# FE1_1S.net
KiCad netlist of a schematic drawn in Altium Designer
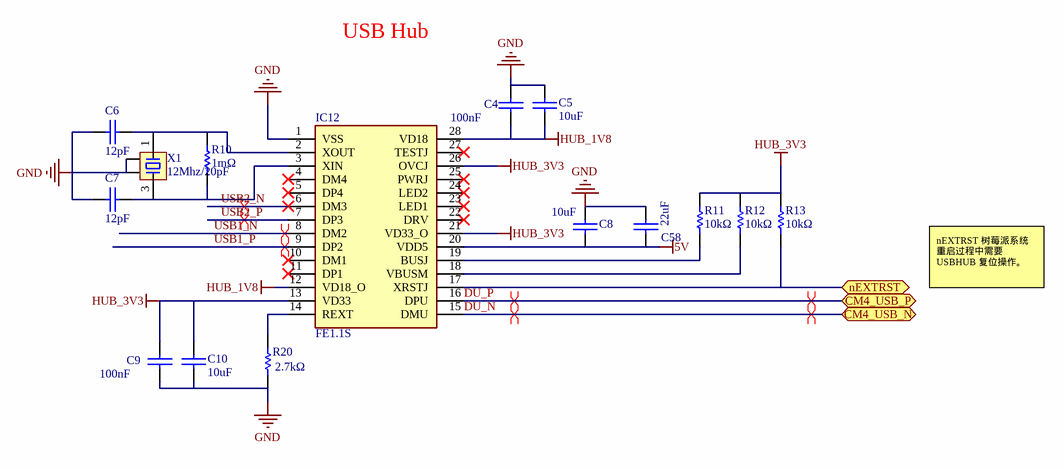
[diagram p0: FE1.1S.SchDoc]

(export (version "E")
  (design (tool "Eeschema 10.0.6"))
  (components
    (comp (ref "C4")
      (value "100nF")
      (footprint "C_0402")
      (description "贴片电容")
      (libsource (lib "IntLib-Passive") (part "Cap_Chip"))
    )
    (comp (ref "C5")
      (value "10uF")
      (footprint "C_0603")
      (description "贴片电容")
      (libsource (lib "IntLib-Passive") (part "Cap_Chip"))
    )
    (comp (ref "C6")
      (value "12pF")
      (footprint "C_0402")
      (description "贴片电容")
      (libsource (lib "IntLib-Passive") (part "Cap_Chip"))
    )
    (comp (ref "C7")
      (value "12pF")
      (footprint "C_0402")
      (description "贴片电容")
      (libsource (lib "IntLib-Passive") (part "Cap_Chip"))
    )
    (comp (ref "C8")
      (value "10uF")
      (footprint "C_0603")
      (description "贴片电容")
      (libsource (lib "IntLib-Passive") (part "Cap_Chip"))
    )
    (comp (ref "C9")
      (value "100nF")
      (footprint "C_0402")
      (description "贴片电容")
      (libsource (lib "IntLib-Passive") (part "Cap_Chip"))
    )
    (comp (ref "C10")
      (value "10uF")
      (footprint "C_0603")
      (description "贴片电容")
      (libsource (lib "IntLib-Passive") (part "Cap_Chip"))
    )
    (comp (ref "C58")
      (value "22uF")
      (footprint "C_0805")
      (description "贴片电容")
      (libsource (lib "IntLib-Passive") (part "Cap_Chip"))
    )
    (comp (ref "IC12")
      (value "FE1.1S")
      (footprint "SamacSys:SOP64P600X175-28N")
      (description "Integrated Circuit")
      (libsource (lib "*") (part "FE1.1S"))
    )
    (comp (ref "R10")
      (value "1mΩ")
      (footprint "R_0402")
      (description "贴片电阻")
      (libsource (lib "IntLib-Passive") (part "Res_Chip"))
    )
    (comp (ref "R11")
      (value "10kΩ")
      (footprint "R_0402")
      (description "贴片电阻")
      (libsource (lib "IntLib-Passive") (part "Res_Chip"))
    )
    (comp (ref "R12")
      (value "10kΩ")
      (footprint "R_0402")
      (description "贴片电阻")
      (libsource (lib "IntLib-Passive") (part "Res_Chip"))
    )
    (comp (ref "R13")
      (value "10kΩ")
      (footprint "R_0402")
      (description "贴片电阻")
      (libsource (lib "IntLib-Passive") (part "Res_Chip"))
    )
    (comp (ref "R20")
      (value "2.7kΩ")
      (footprint "R_0402")
      (description "贴片电阻")
      (libsource (lib "IntLib-Passive") (part "Res_Chip"))
    )
    (comp (ref "X1")
      (value "12Mhz/20pF")
      (footprint "XTAL_3225-4P")
      (description "4脚无源晶振")
      (libsource (lib "IntLib-Active") (part "Crystal_4P"))
    )
  )
  (nets
    (net (code "1") (name "/DU_N") (class "Default")
      (node (ref "IC12") (pin "15") (pinfunction "DMU_15") (pintype "passive"))
    )
    (net (code "2") (name "/DU_P") (class "Default")
      (node (ref "IC12") (pin "16") (pinfunction "DPU_16") (pintype "passive"))
    )
    (net (code "3") (name "/USB1_N") (class "Default")
      (node (ref "IC12") (pin "8") (pinfunction "DM2_8") (pintype "passive"))
    )
    (net (code "4") (name "/USB1_P") (class "Default")
      (node (ref "IC12") (pin "9") (pinfunction "DP2_9") (pintype "passive"))
    )
    (net (code "5") (name "/USB2_N") (class "Default")
      (node (ref "IC12") (pin "6") (pinfunction "DM3_6") (pintype "passive+no_connect"))
    )
    (net (code "6") (name "/USB2_P") (class "Default")
      (node (ref "IC12") (pin "7") (pinfunction "DP3_7") (pintype "passive"))
    )
    (net (code "7") (name "/nEXTRST") (class "Default")
      (node (ref "IC12") (pin "17") (pinfunction "XRSTJ_17") (pintype "passive"))
      (node (ref "R13") (pin "1") (pinfunction "1_1") (pintype "passive"))
    )
    (net (code "8") (name "5V") (class "Default")
      (node (ref "C58") (pin "1") (pinfunction "1_1") (pintype "passive"))
      (node (ref "C8") (pin "2") (pinfunction "2_2") (pintype "passive"))
      (node (ref "IC12") (pin "20") (pinfunction "VDD5_20") (pintype "passive"))
    )
    (net (code "9") (name "GND") (class "Default")
      (node (ref "C10") (pin "2") (pinfunction "2_2") (pintype "passive"))
      (node (ref "C4") (pin "2") (pinfunction "2_2") (pintype "passive"))
      (node (ref "C5") (pin "1") (pinfunction "1_1") (pintype "passive"))
      (node (ref "C58") (pin "2") (pinfunction "2_2") (pintype "passive"))
      (node (ref "C6") (pin "2") (pinfunction "2_2") (pintype "passive"))
      (node (ref "C7") (pin "1") (pinfunction "1_1") (pintype "passive"))
      (node (ref "C8") (pin "1") (pinfunction "1_1") (pintype "passive"))
      (node (ref "C9") (pin "1") (pinfunction "1_1") (pintype "passive"))
      (node (ref "IC12") (pin "1") (pinfunction "VSS_1") (pintype "passive"))
      (node (ref "R20") (pin "1") (pinfunction "1_1") (pintype "passive"))
      (node (ref "X1") (pin "2") (pinfunction "2_2") (pintype "passive"))
      (node (ref "X1") (pin "4") (pinfunction "4_4") (pintype "passive"))
    )
    (net (code "10") (name "HUB_1V8") (class "Default")
      (node (ref "C4") (pin "1") (pinfunction "1_1") (pintype "passive"))
      (node (ref "C5") (pin "2") (pinfunction "2_2") (pintype "passive"))
      (node (ref "IC12") (pin "12") (pinfunction "VD18_O_12") (pintype "passive"))
      (node (ref "IC12") (pin "28") (pinfunction "VD18_28") (pintype "passive"))
    )
    (net (code "11") (name "HUB_3V3") (class "Default")
      (node (ref "C10") (pin "1") (pinfunction "1_1") (pintype "passive"))
      (node (ref "C9") (pin "2") (pinfunction "2_2") (pintype "passive"))
      (node (ref "IC12") (pin "13") (pinfunction "VD33_13") (pintype "passive"))
      (node (ref "IC12") (pin "21") (pinfunction "VD33_O_21") (pintype "passive"))
      (node (ref "IC12") (pin "26") (pinfunction "OVCJ_26") (pintype "passive"))
      (node (ref "R11") (pin "2") (pinfunction "2_2") (pintype "passive"))
      (node (ref "R12") (pin "2") (pinfunction "2_2") (pintype "passive"))
      (node (ref "R13") (pin "2") (pinfunction "2_2") (pintype "passive"))
    )
    (net (code "12") (name "Net-(IC12-BUSJ)") (class "Default")
      (node (ref "IC12") (pin "19") (pinfunction "BUSJ_19") (pintype "passive"))
      (node (ref "R11") (pin "1") (pinfunction "1_1") (pintype "passive"))
    )
    (net (code "13") (name "Net-(IC12-REXT)") (class "Default")
      (node (ref "IC12") (pin "14") (pinfunction "REXT_14") (pintype "passive"))
      (node (ref "R20") (pin "2") (pinfunction "2_2") (pintype "passive"))
    )
    (net (code "14") (name "Net-(IC12-VBUSM)") (class "Default")
      (node (ref "IC12") (pin "18") (pinfunction "VBUSM_18") (pintype "passive"))
      (node (ref "R12") (pin "1") (pinfunction "1_1") (pintype "passive"))
    )
    (net (code "15") (name "Net-(IC12-XIN)") (class "Default")
      (node (ref "C7") (pin "2") (pinfunction "2_2") (pintype "passive"))
      (node (ref "IC12") (pin "3") (pinfunction "XIN_3") (pintype "passive"))
      (node (ref "R10") (pin "1") (pinfunction "1_1") (pintype "passive"))
      (node (ref "X1") (pin "3") (pinfunction "3_3") (pintype "passive"))
    )
    (net (code "16") (name "Net-(IC12-XOUT)") (class "Default")
      (node (ref "C6") (pin "1") (pinfunction "1_1") (pintype "passive"))
      (node (ref "IC12") (pin "2") (pinfunction "XOUT_2") (pintype "passive"))
      (node (ref "R10") (pin "2") (pinfunction "2_2") (pintype "passive"))
      (node (ref "X1") (pin "1") (pinfunction "1_1") (pintype "passive"))
    )
    (net (code "17") (name "unconnected-(IC12-DM1-Pad10)") (class "Default")
      (node (ref "IC12") (pin "10") (pinfunction "DM1_10") (pintype "passive+no_connect"))
    )
    (net (code "18") (name "unconnected-(IC12-DM4-Pad4)") (class "Default")
      (node (ref "IC12") (pin "4") (pinfunction "DM4_4") (pintype "passive+no_connect"))
    )
    (net (code "19") (name "unconnected-(IC12-DP1-Pad11)") (class "Default")
      (node (ref "IC12") (pin "11") (pinfunction "DP1_11") (pintype "passive+no_connect"))
    )
    (net (code "20") (name "unconnected-(IC12-DP4-Pad5)") (class "Default")
      (node (ref "IC12") (pin "5") (pinfunction "DP4_5") (pintype "passive+no_connect"))
    )
    (net (code "21") (name "unconnected-(IC12-DRV-Pad22)") (class "Default")
      (node (ref "IC12") (pin "22") (pinfunction "DRV_22") (pintype "passive+no_connect"))
    )
    (net (code "22") (name "unconnected-(IC12-LED1-Pad23)") (class "Default")
      (node (ref "IC12") (pin "23") (pinfunction "LED1_23") (pintype "passive+no_connect"))
    )
    (net (code "23") (name "unconnected-(IC12-LED2-Pad24)") (class "Default")
      (node (ref "IC12") (pin "24") (pinfunction "LED2_24") (pintype "passive+no_connect"))
    )
    (net (code "24") (name "unconnected-(IC12-PWRJ-Pad25)") (class "Default")
      (node (ref "IC12") (pin "25") (pinfunction "PWRJ_25") (pintype "passive+no_connect"))
    )
    (net (code "25") (name "unconnected-(IC12-TESTJ-Pad27)") (class "Default")
      (node (ref "IC12") (pin "27") (pinfunction "TESTJ_27") (pintype "passive+no_connect"))
    )
  )
)
